# main.net
KiCad netlist of a schematic drawn in EAGLE
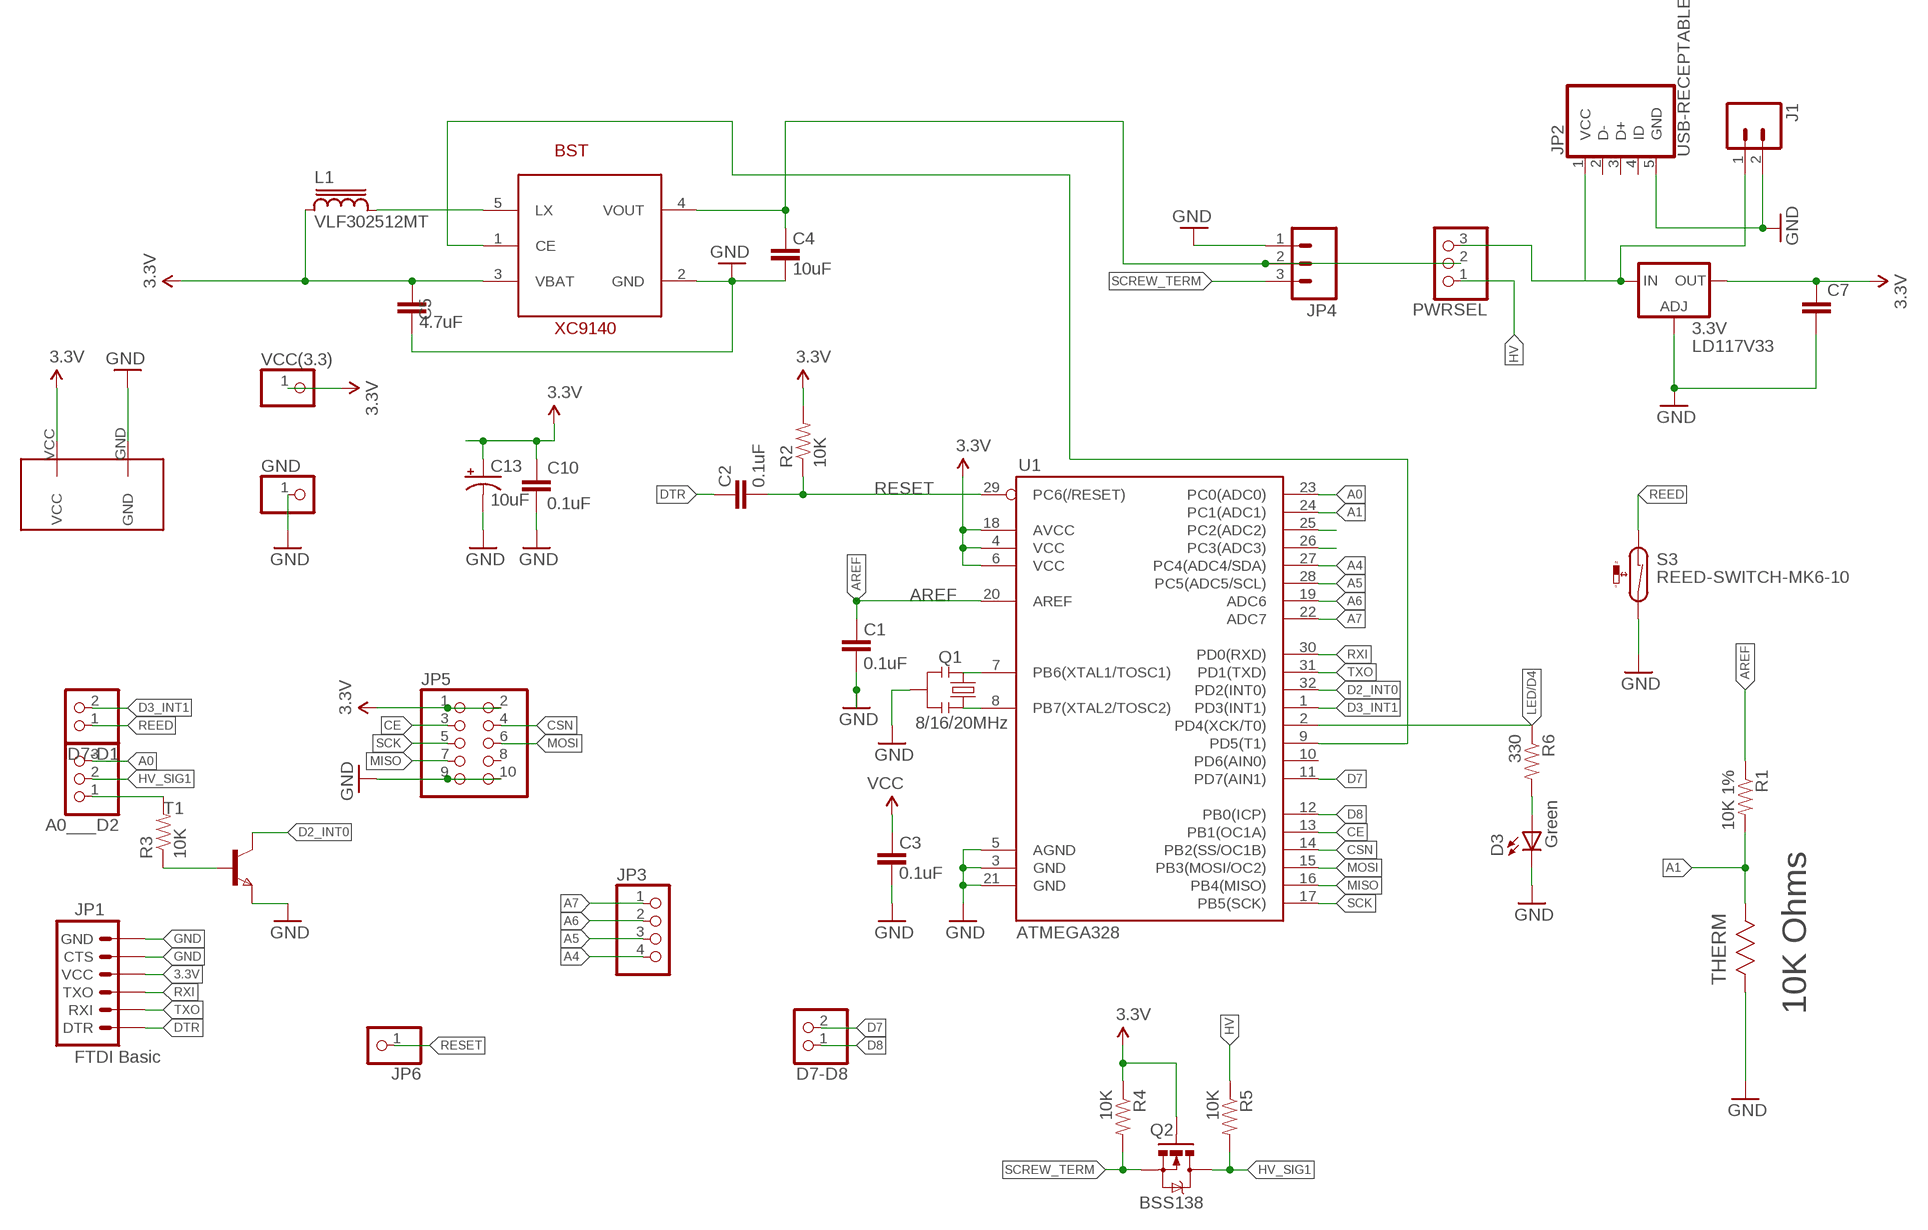
[diagram p0: schematic, sheet 1]

(export (version "E")
  (design (tool "Eeschema 10.0.6"))
  (components
    (comp (ref "3.3V")
      (value "LD117V33")
      (footprint "eagle-import:TO220L1")
      (libsource (lib "eagle-import") (part "LD117A?V"))
    )
    (comp (ref "A0___D2")
      (value "PINHD-1X3")
      (footprint "eagle-import:1X03")
      (libsource (lib "eagle-import") (part "PINHD-1X3"))
    )
    (comp (ref "BST")
      (value "XC9140")
      (footprint "eagle-import:SOT23-5")
      (libsource (lib "eagle-import") (part "XC9140"))
    )
    (comp (ref "C1")
      (value "0.1uF")
      (footprint "eagle-import:0603-CAP")
      (libsource (lib "eagle-import") (part "CAP0603-CAP"))
    )
    (comp (ref "C2")
      (value "0.1uF")
      (footprint "eagle-import:0603-CAP")
      (libsource (lib "eagle-import") (part "CAP0603-CAP"))
    )
    (comp (ref "C3")
      (value "0.1uF")
      (footprint "eagle-import:0603-CAP")
      (libsource (lib "eagle-import") (part "CAP0603-CAP"))
    )
    (comp (ref "C4")
      (value "10uF")
      (footprint "eagle-import:0603-CAP")
      (libsource (lib "eagle-import") (part "CAP0603-CAP"))
    )
    (comp (ref "C5")
      (value "4.7uF")
      (footprint "eagle-import:0603-CAP")
      (libsource (lib "eagle-import") (part "CAP0603-CAP"))
    )
    (comp (ref "C7")
      (value "C2.5/2")
      (footprint "eagle-import:C2.5-2")
      (libsource (lib "eagle-import") (part "C2.5/2"))
    )
    (comp (ref "C10")
      (value "0.1uF")
      (footprint "eagle-import:0603-CAP")
      (libsource (lib "eagle-import") (part "CAP0603-CAP"))
    )
    (comp (ref "C13")
      (value "10uF")
      (footprint "eagle-import:EIA3216")
      (libsource (lib "eagle-import") (part "CAP_POL1206"))
    )
    (comp (ref "D3")
      (value "Green")
      (footprint "eagle-import:0603-LED-ALT1")
      (libsource (lib "eagle-import") (part "LED"))
    )
    (comp (ref "D7-D1")
      (value "PINHD-1X2")
      (footprint "eagle-import:1X02")
      (libsource (lib "eagle-import") (part "PINHD-1X2"))
    )
    (comp (ref "D7-D8")
      (value "PINHD-1X2")
      (footprint "eagle-import:1X02")
      (libsource (lib "eagle-import") (part "PINHD-1X2"))
    )
    (comp (ref "GND")
      (value "PINHD-1X1")
      (footprint "eagle-import:1X01")
      (libsource (lib "eagle-import") (part "PINHD-1X1"))
    )
    (comp (ref "J1")
      (value "M023.5MM")
      (footprint "eagle-import:SCREWTERMINAL-3.5MM-2")
      (libsource (lib "eagle-import") (part "M023.5MM"))
    )
    (comp (ref "JP1")
      (value "FTDI Basic")
      (footprint "eagle-import:1X06")
      (libsource (lib "eagle-import") (part "ARDUINO_SERIAL_PROGRAMPTH"))
    )
    (comp (ref "JP2")
      (value "USB-RECEPTABLE")
      (footprint "eagle-import:FCI-10103594-0001LF")
      (libsource (lib "eagle-import") (part "USB-RECEPTABLE"))
    )
    (comp (ref "JP3")
      (value "PINHD-1X4")
      (footprint "eagle-import:1X04")
      (libsource (lib "eagle-import") (part "PINHD-1X4"))
    )
    (comp (ref "JP4")
      (value "M03SCREW")
      (footprint "eagle-import:SCREWTERMINAL-3.5MM-3")
      (libsource (lib "eagle-import") (part "M03SCREW"))
    )
    (comp (ref "JP5")
      (value "PINHD-2X5")
      (footprint "eagle-import:2X05")
      (libsource (lib "eagle-import") (part "PINHD-2X5"))
    )
    (comp (ref "JP6")
      (value "PINHD-1X1")
      (footprint "eagle-import:1X01")
      (libsource (lib "eagle-import") (part "PINHD-1X1"))
    )
    (comp (ref "L1")
      (value "VLF302512MT")
      (footprint "eagle-import:VLF302512MT")
      (libsource (lib "eagle-import") (part "VLF302512MT"))
    )
    (comp (ref "PWRSEL")
      (value "PINHD-1X3")
      (footprint "eagle-import:1X03")
      (libsource (lib "eagle-import") (part "PINHD-1X3"))
    )
    (comp (ref "Q1")
      (value "8/16/20MHz")
      (footprint "eagle-import:RESONATOR-SMD-1_1")
      (libsource (lib "eagle-import") (part "RESONATOR1{colon}1"))
    )
    (comp (ref "Q2")
      (value "BSS138")
      (footprint "eagle-import:SOT23-3")
      (libsource (lib "eagle-import") (part "MOSFET-NCHANNELSMD"))
    )
    (comp (ref "R1")
      (value "10K 1%")
      (footprint "eagle-import:0603-RES")
      (libsource (lib "eagle-import") (part "RESISTOR0603-RES"))
    )
    (comp (ref "R2")
      (value "10K")
      (footprint "eagle-import:0603-RES")
      (libsource (lib "eagle-import") (part "RESISTOR0603-RES"))
    )
    (comp (ref "R3")
      (value "10K")
      (footprint "eagle-import:0603-RES")
      (libsource (lib "eagle-import") (part "RESISTOR0603-RES"))
    )
    (comp (ref "R4")
      (value "10K")
      (footprint "eagle-import:0603-RES")
      (libsource (lib "eagle-import") (part "RESISTOR0603-RES"))
    )
    (comp (ref "R5")
      (value "10K")
      (footprint "eagle-import:0603-RES")
      (libsource (lib "eagle-import") (part "RESISTOR0603-RES"))
    )
    (comp (ref "R6")
      (value "330")
      (footprint "eagle-import:0603-RES")
      (libsource (lib "eagle-import") (part "RESISTOR0603-RES"))
    )
    (comp (ref "S3")
      (value "REED-SWITCH-MK6-10")
      (footprint "eagle-import:MK6-10")
      (libsource (lib "eagle-import") (part "REED-SWITCH-MK6-10"))
    )
    (comp (ref "T1")
      (value "NPNSOT323")
      (footprint "eagle-import:SOT323")
      (fields (field (name "MPN") "DSS4160U-7"))
      (libsource (lib "eagle-import") (part "NPNSOT323"))
    )
    (comp (ref "THERM")
      (value "10K Ohms")
      (footprint "eagle-import:RESC1608X95N")
      (fields (field (name "MPN") "NTCS0603E3103HMT") (field (name "TOLERANCE") "± 3%"))
      (libsource (lib "eagle-import") (part "NTCS0603E3103HMT"))
    )
    (comp (ref "U$1")
      (value "BAT")
      (footprint "eagle-import:AAABATTERY")
      (libsource (lib "eagle-import") (part "BAT"))
    )
    (comp (ref "U1")
      (value "ATMEGA328")
      (footprint "eagle-import:TQFP32-08")
      (libsource (lib "eagle-import") (part "ATMEGA168"))
    )
    (comp (ref "VCC(3.3)")
      (value "PINHD-1X1")
      (footprint "eagle-import:1X01")
      (libsource (lib "eagle-import") (part "PINHD-1X1"))
    )
  )
  (nets
    (net (code "1") (name "3.3V") (class "Default")
      (node (ref "3.3V") (pin "2") (pinfunction "OUT_2") (pintype "passive"))
      (node (ref "BST") (pin "3") (pinfunction "VBAT_3") (pintype "bidirectional"))
      (node (ref "C10") (pin "1") (pinfunction "1_1") (pintype "passive"))
      (node (ref "C13") (pin "A") (pinfunction "+_A") (pintype "passive"))
      (node (ref "C3") (pin "2") (pinfunction "2_2") (pintype "passive"))
      (node (ref "C5") (pin "2") (pinfunction "2_2") (pintype "passive"))
      (node (ref "C7") (pin "1") (pinfunction "1_1") (pintype "passive"))
      (node (ref "JP1") (pin "4") (pinfunction "VCC_4") (pintype "passive"))
      (node (ref "JP5") (pin "1") (pinfunction "1_1") (pintype "passive"))
      (node (ref "JP5") (pin "2") (pinfunction "2_2") (pintype "passive"))
      (node (ref "L1") (pin "1") (pinfunction "1_1") (pintype "passive"))
      (node (ref "Q2") (pin "1") (pinfunction "G_1") (pintype "passive"))
      (node (ref "R2") (pin "2") (pinfunction "2_2") (pintype "passive"))
      (node (ref "R4") (pin "1") (pinfunction "1_1") (pintype "passive"))
      (node (ref "U$1") (pin "VCC") (pinfunction "VCC_VCC") (pintype "bidirectional"))
      (node (ref "U1") (pin "18") (pinfunction "AVCC_18") (pintype "bidirectional"))
      (node (ref "U1") (pin "4") (pinfunction "VCC_4") (pintype "bidirectional"))
      (node (ref "U1") (pin "6") (pinfunction "VCC_6") (pintype "bidirectional"))
      (node (ref "VCC(3.3)") (pin "1") (pinfunction "1_1") (pintype "passive"))
    )
    (net (code "2") (name "A0") (class "Default")
      (node (ref "A0___D2") (pin "3") (pinfunction "3_3") (pintype "passive"))
      (node (ref "U1") (pin "23") (pinfunction "PC0(ADC0)_23") (pintype "bidirectional"))
    )
    (net (code "3") (name "A1") (class "Default")
      (node (ref "R1") (pin "2") (pinfunction "2_2") (pintype "passive"))
      (node (ref "THERM") (pin "1") (pinfunction "1_1") (pintype "passive"))
      (node (ref "U1") (pin "24") (pinfunction "PC1(ADC1)_24") (pintype "bidirectional"))
    )
    (net (code "4") (name "A4") (class "Default")
      (node (ref "JP3") (pin "4") (pinfunction "4_4") (pintype "passive"))
      (node (ref "U1") (pin "27") (pinfunction "PC4(ADC4/SDA)_27") (pintype "bidirectional"))
    )
    (net (code "5") (name "A5") (class "Default")
      (node (ref "JP3") (pin "3") (pinfunction "3_3") (pintype "passive"))
      (node (ref "U1") (pin "28") (pinfunction "PC5(ADC5/SCL)_28") (pintype "bidirectional"))
    )
    (net (code "6") (name "A6") (class "Default")
      (node (ref "JP3") (pin "2") (pinfunction "2_2") (pintype "passive"))
      (node (ref "U1") (pin "19") (pinfunction "ADC6_19") (pintype "bidirectional"))
    )
    (net (code "7") (name "A7") (class "Default")
      (node (ref "JP3") (pin "1") (pinfunction "1_1") (pintype "passive"))
      (node (ref "U1") (pin "22") (pinfunction "ADC7_22") (pintype "bidirectional"))
    )
    (net (code "8") (name "AREF") (class "Default")
      (node (ref "C1") (pin "2") (pinfunction "2_2") (pintype "passive"))
      (node (ref "R1") (pin "1") (pinfunction "1_1") (pintype "passive"))
      (node (ref "U1") (pin "20") (pinfunction "AREF_20") (pintype "bidirectional"))
    )
    (net (code "9") (name "CE") (class "Default")
      (node (ref "JP5") (pin "3") (pinfunction "3_3") (pintype "passive"))
      (node (ref "U1") (pin "13") (pinfunction "PB1(OC1A)_13") (pintype "bidirectional"))
    )
    (net (code "10") (name "CSN") (class "Default")
      (node (ref "JP5") (pin "4") (pinfunction "4_4") (pintype "passive"))
      (node (ref "U1") (pin "14") (pinfunction "PB2(SS/OC1B)_14") (pintype "bidirectional"))
    )
    (net (code "11") (name "D2_INT0") (class "Default")
      (node (ref "T1") (pin "1") (pinfunction "C_1") (pintype "passive"))
      (node (ref "U1") (pin "32") (pinfunction "PD2(INT0)_32") (pintype "bidirectional"))
    )
    (net (code "12") (name "D3_INT1") (class "Default")
      (node (ref "D7-D1") (pin "2") (pinfunction "2_2") (pintype "passive"))
      (node (ref "U1") (pin "1") (pinfunction "PD3(INT1)_1") (pintype "bidirectional"))
    )
    (net (code "13") (name "D7") (class "Default")
      (node (ref "D7-D8") (pin "2") (pinfunction "2_2") (pintype "passive"))
      (node (ref "U1") (pin "11") (pinfunction "PD7(AIN1)_11") (pintype "bidirectional"))
    )
    (net (code "14") (name "D8") (class "Default")
      (node (ref "D7-D8") (pin "1") (pinfunction "1_1") (pintype "passive"))
      (node (ref "U1") (pin "12") (pinfunction "PB0(ICP)_12") (pintype "bidirectional"))
    )
    (net (code "15") (name "DTR") (class "Default")
      (node (ref "C2") (pin "2") (pinfunction "2_2") (pintype "passive"))
      (node (ref "JP1") (pin "1") (pinfunction "DTR_1") (pintype "passive"))
    )
    (net (code "16") (name "GND") (class "Default")
      (node (ref "3.3V") (pin "1") (pinfunction "ADJ_1") (pintype "input"))
      (node (ref "BST") (pin "2") (pinfunction "GND_2") (pintype "bidirectional"))
      (node (ref "C1") (pin "1") (pinfunction "1_1") (pintype "passive"))
      (node (ref "C10") (pin "2") (pinfunction "2_2") (pintype "passive"))
      (node (ref "C13") (pin "C") (pinfunction "-_C") (pintype "passive"))
      (node (ref "C3") (pin "1") (pinfunction "1_1") (pintype "passive"))
      (node (ref "C4") (pin "1") (pinfunction "1_1") (pintype "passive"))
      (node (ref "C5") (pin "1") (pinfunction "1_1") (pintype "passive"))
      (node (ref "C7") (pin "2") (pinfunction "2_2") (pintype "passive"))
      (node (ref "D3") (pin "C") (pinfunction "C_C") (pintype "passive"))
      (node (ref "GND") (pin "1") (pinfunction "1_1") (pintype "passive"))
      (node (ref "J1") (pin "2") (pinfunction "2_2") (pintype "passive"))
      (node (ref "JP1") (pin "5") (pinfunction "CTS_5") (pintype "passive"))
      (node (ref "JP1") (pin "6") (pinfunction "GND_6") (pintype "passive"))
      (node (ref "JP2") (pin "5") (pinfunction "GND_5") (pintype "bidirectional"))
      (node (ref "JP4") (pin "1") (pinfunction "1_1") (pintype "passive"))
      (node (ref "JP5") (pin "10") (pinfunction "10_10") (pintype "passive"))
      (node (ref "JP5") (pin "9") (pinfunction "9_9") (pintype "passive"))
      (node (ref "Q1") (pin "2") (pinfunction "2_2") (pintype "passive"))
      (node (ref "S3") (pin "2") (pinfunction "2_2") (pintype "passive"))
      (node (ref "T1") (pin "3") (pinfunction "E_3") (pintype "passive"))
      (node (ref "THERM") (pin "2") (pinfunction "2_2") (pintype "passive"))
      (node (ref "U$1") (pin "GND") (pinfunction "GND_GND") (pintype "bidirectional"))
      (node (ref "U1") (pin "21") (pinfunction "GND_21") (pintype "bidirectional"))
      (node (ref "U1") (pin "3") (pinfunction "GND_3") (pintype "bidirectional"))
      (node (ref "U1") (pin "5") (pinfunction "AGND_5") (pintype "bidirectional"))
    )
    (net (code "17") (name "HV") (class "Default")
      (node (ref "PWRSEL") (pin "1") (pinfunction "1_1") (pintype "passive"))
      (node (ref "R5") (pin "1") (pinfunction "1_1") (pintype "passive"))
    )
    (net (code "18") (name "HV_SIG1") (class "Default")
      (node (ref "A0___D2") (pin "2") (pinfunction "2_2") (pintype "passive"))
      (node (ref "Q2") (pin "3") (pinfunction "D_3") (pintype "passive"))
      (node (ref "R5") (pin "2") (pinfunction "2_2") (pintype "passive"))
    )
    (net (code "19") (name "LED{slash}D4") (class "Default")
      (node (ref "R6") (pin "1") (pinfunction "1_1") (pintype "passive"))
      (node (ref "U1") (pin "2") (pinfunction "PD4(XCK/T0)_2") (pintype "bidirectional"))
    )
    (net (code "20") (name "MISO") (class "Default")
      (node (ref "JP5") (pin "7") (pinfunction "7_7") (pintype "passive"))
      (node (ref "U1") (pin "16") (pinfunction "PB4(MISO)_16") (pintype "bidirectional"))
    )
    (net (code "21") (name "MOSI") (class "Default")
      (node (ref "JP5") (pin "6") (pinfunction "6_6") (pintype "passive"))
      (node (ref "U1") (pin "15") (pinfunction "PB3(MOSI/OC2)_15") (pintype "bidirectional"))
    )
    (net (code "22") (name "Net-(3.3V-IN)") (class "Default")
      (node (ref "3.3V") (pin "3") (pinfunction "IN_3") (pintype "input"))
      (node (ref "J1") (pin "1") (pinfunction "1_1") (pintype "passive"))
      (node (ref "JP2") (pin "1") (pinfunction "VCC_1") (pintype "bidirectional"))
      (node (ref "PWRSEL") (pin "3") (pinfunction "3_3") (pintype "passive"))
    )
    (net (code "23") (name "Net-(A0___D2-Pad1)") (class "Default")
      (node (ref "A0___D2") (pin "1") (pinfunction "1_1") (pintype "passive"))
      (node (ref "R3") (pin "2") (pinfunction "2_2") (pintype "passive"))
    )
    (net (code "24") (name "Net-(BST-CE)") (class "Default")
      (node (ref "BST") (pin "1") (pinfunction "CE_1") (pintype "bidirectional"))
      (node (ref "U1") (pin "9") (pinfunction "PD5(T1)_9") (pintype "bidirectional"))
    )
    (net (code "25") (name "Net-(BST-LX)") (class "Default")
      (node (ref "BST") (pin "5") (pinfunction "LX_5") (pintype "bidirectional"))
      (node (ref "L1") (pin "2") (pinfunction "2_2") (pintype "passive"))
    )
    (net (code "26") (name "Net-(BST-VOUT)") (class "Default")
      (node (ref "BST") (pin "4") (pinfunction "VOUT_4") (pintype "bidirectional"))
      (node (ref "C4") (pin "2") (pinfunction "2_2") (pintype "passive"))
      (node (ref "JP4") (pin "2") (pinfunction "2_2") (pintype "passive"))
      (node (ref "PWRSEL") (pin "2") (pinfunction "2_2") (pintype "passive"))
    )
    (net (code "27") (name "Net-(D3-PadA)") (class "Default")
      (node (ref "D3") (pin "A") (pinfunction "A_A") (pintype "passive"))
      (node (ref "R6") (pin "2") (pinfunction "2_2") (pintype "passive"))
    )
    (net (code "28") (name "Net-(T1-B)") (class "Default")
      (node (ref "R3") (pin "1") (pinfunction "1_1") (pintype "passive"))
      (node (ref "T1") (pin "2") (pinfunction "B_2") (pintype "passive"))
    )
    (net (code "29") (name "Net-(U1-PB6(XTAL1{slash}TOSC1))") (class "Default")
      (node (ref "Q1") (pin "1") (pinfunction "1_1") (pintype "passive"))
      (node (ref "U1") (pin "7") (pinfunction "PB6(XTAL1/TOSC1)_7") (pintype "bidirectional"))
    )
    (net (code "30") (name "Net-(U1-PB7(XTAL2{slash}TOSC2))") (class "Default")
      (node (ref "Q1") (pin "3") (pinfunction "3_3") (pintype "passive"))
      (node (ref "U1") (pin "8") (pinfunction "PB7(XTAL2/TOSC2)_8") (pintype "bidirectional"))
    )
    (net (code "31") (name "REED") (class "Default")
      (node (ref "D7-D1") (pin "1") (pinfunction "1_1") (pintype "passive"))
      (node (ref "S3") (pin "1") (pinfunction "1_1") (pintype "passive"))
    )
    (net (code "32") (name "RESET") (class "Default")
      (node (ref "C2") (pin "1") (pinfunction "1_1") (pintype "passive"))
      (node (ref "JP6") (pin "1") (pinfunction "1_1") (pintype "passive"))
      (node (ref "R2") (pin "1") (pinfunction "1_1") (pintype "passive"))
      (node (ref "U1") (pin "29") (pinfunction "PC6(/RESET)_29") (pintype "bidirectional"))
    )
    (net (code "33") (name "RXI") (class "Default")
      (node (ref "JP1") (pin "3") (pinfunction "TXO_3") (pintype "passive"))
      (node (ref "U1") (pin "30") (pinfunction "PD0(RXD)_30") (pintype "bidirectional"))
    )
    (net (code "34") (name "SCK") (class "Default")
      (node (ref "JP5") (pin "5") (pinfunction "5_5") (pintype "passive"))
      (node (ref "U1") (pin "17") (pinfunction "PB5(SCK)_17") (pintype "bidirectional"))
    )
    (net (code "35") (name "SCREW_TERM") (class "Default")
      (node (ref "JP4") (pin "3") (pinfunction "3_3") (pintype "passive"))
      (node (ref "Q2") (pin "2") (pinfunction "S_2") (pintype "passive"))
      (node (ref "R4") (pin "2") (pinfunction "2_2") (pintype "passive"))
    )
    (net (code "36") (name "TXO") (class "Default")
      (node (ref "JP1") (pin "2") (pinfunction "RXI_2") (pintype "passive"))
      (node (ref "U1") (pin "31") (pinfunction "PD1(TXD)_31") (pintype "bidirectional"))
    )
    (net (code "37") (name "unconnected-(JP2-D+-Pad3)") (class "Default")
      (node (ref "JP2") (pin "3") (pinfunction "D+_3") (pintype "bidirectional"))
    )
    (net (code "38") (name "unconnected-(JP2-D--Pad2)") (class "Default")
      (node (ref "JP2") (pin "2") (pinfunction "D-_2") (pintype "bidirectional"))
    )
    (net (code "39") (name "unconnected-(JP2-ID-Pad4)") (class "Default")
      (node (ref "JP2") (pin "4") (pinfunction "ID_4") (pintype "bidirectional"))
    )
    (net (code "40") (name "unconnected-(JP5-Pad8)") (class "Default")
      (node (ref "JP5") (pin "8") (pinfunction "8_8") (pintype "passive"))
    )
    (net (code "41") (name "unconnected-(U1-PC2(ADC2)-Pad25)") (class "Default")
      (node (ref "U1") (pin "25") (pinfunction "PC2(ADC2)_25") (pintype "bidirectional"))
    )
    (net (code "42") (name "unconnected-(U1-PC3(ADC3)-Pad26)") (class "Default")
      (node (ref "U1") (pin "26") (pinfunction "PC3(ADC3)_26") (pintype "bidirectional"))
    )
    (net (code "43") (name "unconnected-(U1-PD6(AIN0)-Pad10)") (class "Default")
      (node (ref "U1") (pin "10") (pinfunction "PD6(AIN0)_10") (pintype "bidirectional"))
    )
  )
)
